# SH1_-_Buck_Converter.net
KiCad netlist of a schematic drawn in Altium Designer
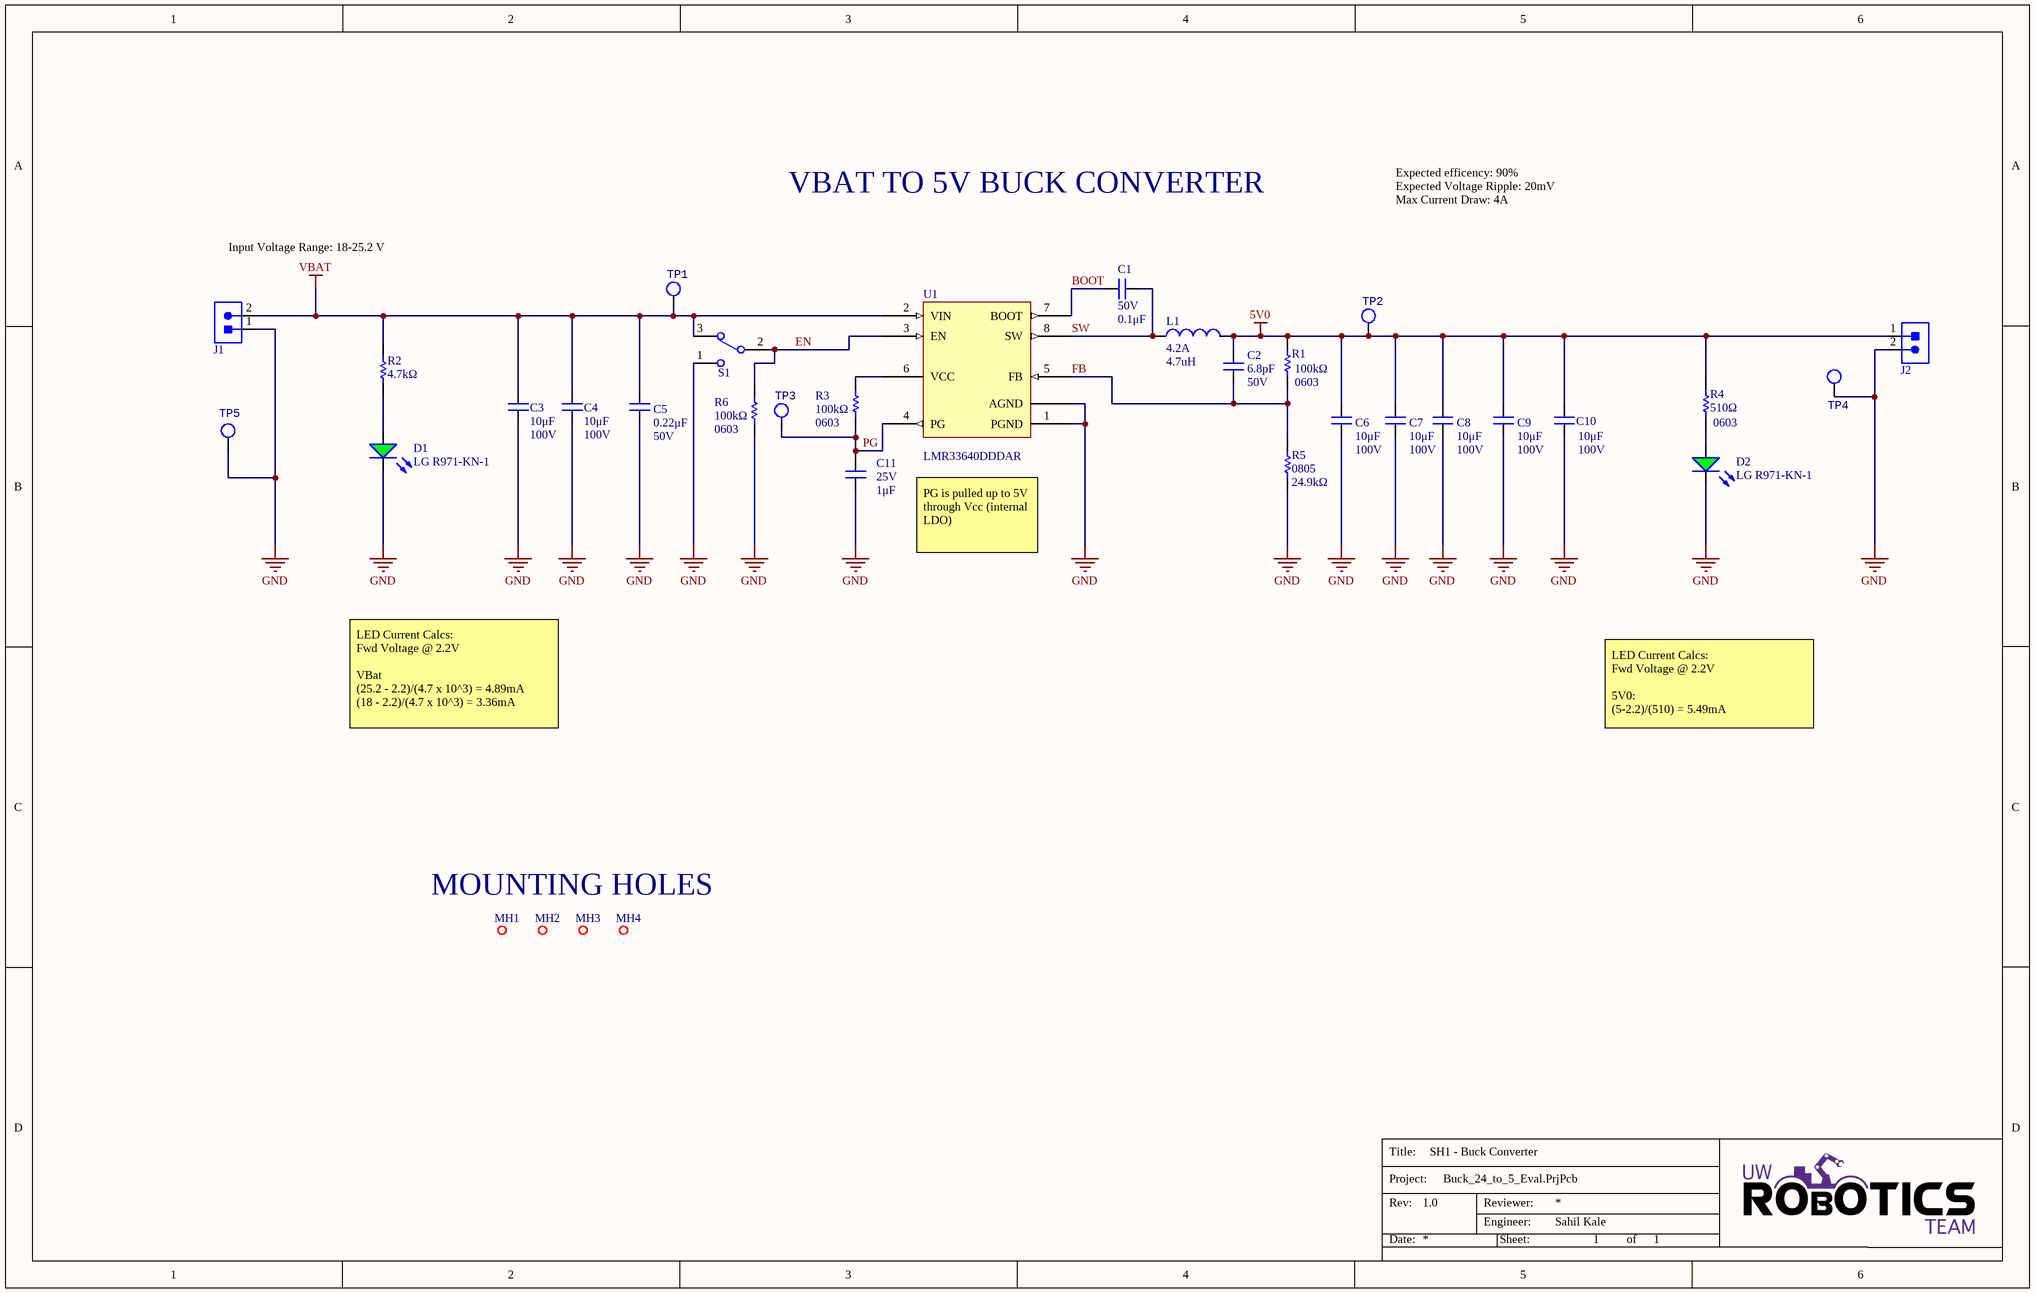
[diagram p0: SH1 - Buck Converter.SchDoc]

(export (version "E")
  (design (tool "Eeschema 10.0.6"))
  (components
    (comp (ref "C1")
      (value "0.1μF")
      (footprint "CAP0603")
      (description "CAP CER 0.1UF 50V X7R 0603")
      (fields (field (name "VOLTAGE RATING") "50V") (field (name "Comment") "CAP_0.1uF_50V_0603"))
      (libsource (lib "UWRT_Schematic_Library_2020") (part "CAP_0.1uF_50V_0603"))
    )
    (comp (ref "C2")
      (value "6.8pF")
      (footprint "CAP0603")
      (description "CAP CER 6.8PF 50V")
      (fields (field (name "VOLTAGE RATING") "50V") (field (name "Comment") "CAP_6.8pF_50V_0603"))
      (libsource (lib "UWRT_Schematic_Library_2020") (part "CAP_6.8pF_50V_0603"))
    )
    (comp (ref "C3")
      (value "10μF")
      (footprint "CAP1210")
      (description "CAP CER 10uF 100V X7S 10% 1210")
      (fields (field (name "VOLTAGE RATING") "100V") (field (name "Comment") "CAP_10uF_100V_1210"))
      (libsource (lib "UWRT_Schematic_Library_2020") (part "CAP_10uF_100V_1210"))
    )
    (comp (ref "C4")
      (value "10μF")
      (footprint "CAP1210")
      (description "CAP CER 10uF 100V X7S 10% 1210")
      (fields (field (name "VOLTAGE RATING") "100V") (field (name "Comment") "CAP_10uF_100V_1210"))
      (libsource (lib "UWRT_Schematic_Library_2020") (part "CAP_10uF_100V_1210"))
    )
    (comp (ref "C5")
      (value "0.22μF")
      (footprint "CAP2012")
      (description "CAP CER 0.22UF 50V X7R 0805")
      (fields
        (field (name "LCSC PART #") "C5378")
        (field (name "VOLTAGE RATING") "50V")
        (field (name "Comment") "CAP_0.22uF_50V_0805")
      )
      (libsource (lib "UWRT_Schematic_Library_2020") (part "CAP_0.22uF_50V_0805"))
    )
    (comp (ref "C6")
      (value "10μF")
      (footprint "CAP1210")
      (description "CAP CER 10uF 100V X7S 10% 1210")
      (fields (field (name "VOLTAGE RATING") "100V") (field (name "Comment") "CAP_10uF_100V_1210"))
      (libsource (lib "UWRT_Schematic_Library_2020") (part "CAP_10uF_100V_1210"))
    )
    (comp (ref "C7")
      (value "10μF")
      (footprint "CAP1210")
      (description "CAP CER 10uF 100V X7S 10% 1210")
      (fields (field (name "VOLTAGE RATING") "100V") (field (name "Comment") "CAP_10uF_100V_1210"))
      (libsource (lib "UWRT_Schematic_Library_2020") (part "CAP_10uF_100V_1210"))
    )
    (comp (ref "C8")
      (value "10μF")
      (footprint "CAP1210")
      (description "CAP CER 10uF 100V X7S 10% 1210")
      (fields (field (name "VOLTAGE RATING") "100V") (field (name "Comment") "CAP_10uF_100V_1210"))
      (libsource (lib "UWRT_Schematic_Library_2020") (part "CAP_10uF_100V_1210"))
    )
    (comp (ref "C9")
      (value "10μF")
      (footprint "CAP1210")
      (description "CAP CER 10uF 100V X7S 10% 1210")
      (fields (field (name "VOLTAGE RATING") "100V") (field (name "Comment") "CAP_10uF_100V_1210"))
      (libsource (lib "UWRT_Schematic_Library_2020") (part "CAP_10uF_100V_1210"))
    )
    (comp (ref "C10")
      (value "10μF")
      (footprint "CAP1210")
      (description "CAP CER 10uF 100V X7S 10% 1210")
      (fields (field (name "VOLTAGE RATING") "100V") (field (name "Comment") "CAP_10uF_100V_1210"))
      (libsource (lib "UWRT_Schematic_Library_2020") (part "CAP_10uF_100V_1210"))
    )
    (comp (ref "C11")
      (value "1μF")
      (footprint "CAP0603")
      (description "CAP CER 1UF 25V X5R 0603")
      (fields (field (name "VOLTAGE RATING") "25V") (field (name "Comment") "CAP_1uF_25V_0603"))
      (libsource (lib "UWRT_Schematic_Library_2020") (part "CAP_1uF_25V_0603"))
    )
    (comp (ref "D1")
      (value "LED_GREEN")
      (footprint "LED_0805_GREEN")
      (description "LED GREEN DIFFUSED 0805 SMD")
      (fields (field (name "MANUFACTURER PART NUMBER 1") "LG R971-KN-1"))
      (libsource (lib "UWRT_Schematic_Library_2020") (part "LED_GREEN"))
    )
    (comp (ref "D2")
      (value "LED_GREEN")
      (footprint "LED_0805_GREEN")
      (description "LED GREEN DIFFUSED 0805 SMD")
      (fields (field (name "MANUFACTURER PART NUMBER 1") "LG R971-KN-1"))
      (libsource (lib "UWRT_Schematic_Library_2020") (part "LED_GREEN"))
    )
    (comp (ref "J1")
      (value "CON_2POS_SCREW_TERM")
      (footprint "1935161")
      (description "TERM BLK 2POS SIDE ENTRY 5MM")
      (libsource (lib "") (part "CON_2POS_SCREW_TERM_1"))
    )
    (comp (ref "J2")
      (value "CON_2POS_SCREW_TERM")
      (footprint "1935161")
      (description "TERM BLK 2POS SIDE ENTRY 5MM")
      (libsource (lib "UWRT_Schematic_Library_2020") (part "CON_2POS_SCREW_TERM"))
    )
    (comp (ref "L1")
      (value "IND_4.7uH_4.2A")
      (footprint "VLS6045EX-4R7M")
      (description "FIXED IND 4.7UH 4.2A 35MOHM SMD")
      (fields
        (field (name "MANUFACTURER") "TDK")
        (field (name "TOLERANCE") "20%")
        (field (name "RATED CURRENT-MAX") "4.2A")
        (field (name "INDUCTANCE-NOM (L)") "4.7uH")
      )
      (libsource (lib "UWRT_Schematic_Library_2020") (part "IND_4.7uH_4.2A"))
    )
    (comp (ref "MH1")
      (value "MOUNTING_HOLE_M3")
      (footprint "MOUNTING_HOLE_3mm")
      (libsource (lib "UWRT_Schematic_Library_2020") (part "MOUNTING_HOLE_M3"))
    )
    (comp (ref "MH2")
      (value "MOUNTING_HOLE_M3")
      (footprint "MOUNTING_HOLE_3mm")
      (libsource (lib "UWRT_Schematic_Library_2020") (part "MOUNTING_HOLE_M3"))
    )
    (comp (ref "MH3")
      (value "MOUNTING_HOLE_M3")
      (footprint "MOUNTING_HOLE_3mm")
      (libsource (lib "UWRT_Schematic_Library_2020") (part "MOUNTING_HOLE_M3"))
    )
    (comp (ref "MH4")
      (value "MOUNTING_HOLE_M3")
      (footprint "MOUNTING_HOLE_3mm")
      (libsource (lib "UWRT_Schematic_Library_2020") (part "MOUNTING_HOLE_M3"))
    )
    (comp (ref "R1")
      (value "100kΩ")
      (footprint "RESC0603")
      (description "RES 100K OHM 1% 1/10W 0603")
      (fields (field (name "PACKAGE/FOOTPRINT") "0603") (field (name "Comment") "RES_100kΩ_0603_1%"))
      (libsource (lib "UWRT_Schematic_Library_2020") (part "RES_100kΩ_0603_1%"))
    )
    (comp (ref "R2")
      (value "4.7kΩ")
      (footprint "RESC0603")
      (description "RES 4.7K OHM 5% 1/10W 0603")
      (fields (field (name "Comment") "RES_4.7kΩ_0603"))
      (libsource (lib "UWRT_Schematic_Library_2020") (part "RES_4.7kΩ_0603_5%"))
    )
    (comp (ref "R3")
      (value "100kΩ")
      (footprint "RESC0603")
      (description "RES 100K OHM 1% 1/10W 0603")
      (fields (field (name "PACKAGE/FOOTPRINT") "0603") (field (name "Comment") "RES_100kΩ_0603_1%"))
      (libsource (lib "UWRT_Schematic_Library_2020") (part "RES_100kΩ_0603_1%"))
    )
    (comp (ref "R4")
      (value "510Ω")
      (footprint "RESC0603")
      (description "RES 510 OHM 5% 1/10W 0603")
      (fields (field (name "PACKAGE") "0603") (field (name "Comment") "RES_510Ω_0603"))
      (libsource (lib "UWRT_Schematic_Library_2020") (part "RES_510Ω_0603_5%"))
    )
    (comp (ref "R5")
      (value "24.9kΩ")
      (footprint "RESC0805")
      (description "RES 24.9K OHM 1% 1/8W 0805")
      (fields (field (name "PACKAGE/FOOTPRINT") "0805") (field (name "Comment") "RES_24.9kΩ_0805_1%_1"))
      (libsource (lib "UWRT_Schematic_Library_2020") (part "RES_24.9kΩ_0805_1%_1"))
    )
    (comp (ref "R6")
      (value "100kΩ")
      (footprint "RESC0603")
      (description "RES 100K OHM 1% 1/10W 0603")
      (fields (field (name "PACKAGE/FOOTPRINT") "0603") (field (name "Comment") "RES_100kΩ_0603_1%"))
      (libsource (lib "UWRT_Schematic_Library_2020") (part "RES_100kΩ_0603_1%"))
    )
    (comp (ref "S1")
      (value "SW_TOGGLE_SPDT")
      (footprint "100SP1T1B4M2QE")
      (description "SWITCH TOGGLE SPDT 5A 120V")
      (libsource (lib "UWRT_Schematic_Library_2020") (part "SW_TOGGLE_SPDT"))
    )
    (comp (ref "TP1")
      (value "TESTPOINT_LOOP")
      (footprint "TESTPOINT_LOOP")
      (description "TESTPOINT THRUHOLE")
      (libsource (lib "UWRT_Schematic_Library_2020") (part "TESTPOINT_LOOP"))
    )
    (comp (ref "TP2")
      (value "TESTPOINT_LOOP")
      (footprint "TESTPOINT_LOOP")
      (description "TESTPOINT THRUHOLE")
      (libsource (lib "UWRT_Schematic_Library_2020") (part "TESTPOINT_LOOP"))
    )
    (comp (ref "TP3")
      (value "TESTPOINT_LOOP")
      (footprint "TESTPOINT_LOOP")
      (description "TESTPOINT THRUHOLE")
      (libsource (lib "UWRT_Schematic_Library_2020") (part "TESTPOINT_LOOP"))
    )
    (comp (ref "TP4")
      (value "TESTPOINT_LOOP")
      (footprint "TESTPOINT_LOOP")
      (description "TESTPOINT THRUHOLE")
      (libsource (lib "UWRT_Schematic_Library_2020") (part "TESTPOINT_LOOP"))
    )
    (comp (ref "TP5")
      (value "TESTPOINT_LOOP")
      (footprint "TESTPOINT_LOOP")
      (description "TESTPOINT THRUHOLE")
      (libsource (lib "UWRT_Schematic_Library_2020") (part "TESTPOINT_LOOP"))
    )
    (comp (ref "U1")
      (value "BUCK_LMR33640DDDAR")
      (footprint "8-SO PowerPad")
      (description "IC REG BUCK ADJUSTABLE 4A 8SOPWR")
      (fields
        (field (name "MANUFACTURER") "Texas Instruments")
        (field (name "MANUFACTURER PART NUMBER 1") "LMR33640DDDAR")
      )
      (libsource (lib "UWRT_Schematic_Library_2020") (part "BUCK_LMR33640DDDAR"))
    )
  )
  (nets
    (net (code "1") (name "/BOOT") (class "Default")
      (node (ref "C1") (pin "1") (pinfunction "1_1") (pintype "passive"))
      (node (ref "U1") (pin "7") (pinfunction "BOOT_7") (pintype "output"))
    )
    (net (code "2") (name "/EN") (class "Default")
      (node (ref "R6") (pin "2") (pinfunction "2_2") (pintype "passive"))
      (node (ref "S1") (pin "2") (pinfunction "2_2") (pintype "passive"))
      (node (ref "U1") (pin "3") (pinfunction "EN_3") (pintype "input"))
    )
    (net (code "3") (name "/FB") (class "Default")
      (node (ref "C2") (pin "1") (pinfunction "1_1") (pintype "passive"))
      (node (ref "R1") (pin "1") (pinfunction "1_1") (pintype "passive"))
      (node (ref "R5") (pin "2") (pinfunction "2_2") (pintype "passive"))
      (node (ref "U1") (pin "5") (pinfunction "FB_5") (pintype "input"))
    )
    (net (code "4") (name "/PG") (class "Default")
      (node (ref "C11") (pin "2") (pinfunction "2_2") (pintype "passive"))
      (node (ref "R3") (pin "1") (pinfunction "1_1") (pintype "passive"))
      (node (ref "TP3") (pin "1") (pintype "passive"))
      (node (ref "U1") (pin "4") (pinfunction "PG_4") (pintype "output"))
    )
    (net (code "5") (name "/SW") (class "Default")
      (node (ref "C1") (pin "2") (pinfunction "2_2") (pintype "passive"))
      (node (ref "L1") (pin "1") (pinfunction "1_1") (pintype "passive"))
      (node (ref "U1") (pin "8") (pinfunction "SW_8") (pintype "output"))
    )
    (net (code "6") (name "5V0") (class "Default")
      (node (ref "C10") (pin "2") (pinfunction "2_2") (pintype "passive"))
      (node (ref "C2") (pin "2") (pinfunction "2_2") (pintype "passive"))
      (node (ref "C6") (pin "2") (pinfunction "2_2") (pintype "passive"))
      (node (ref "C7") (pin "2") (pinfunction "2_2") (pintype "passive"))
      (node (ref "C8") (pin "2") (pinfunction "2_2") (pintype "passive"))
      (node (ref "C9") (pin "2") (pinfunction "2_2") (pintype "passive"))
      (node (ref "J2") (pin "1") (pinfunction "1_1") (pintype "passive"))
      (node (ref "L1") (pin "2") (pinfunction "2_2") (pintype "passive"))
      (node (ref "R1") (pin "2") (pinfunction "2_2") (pintype "passive"))
      (node (ref "R4") (pin "1") (pinfunction "1_1") (pintype "passive"))
      (node (ref "TP2") (pin "1") (pintype "passive"))
    )
    (net (code "7") (name "GND") (class "Default")
      (node (ref "C10") (pin "1") (pinfunction "1_1") (pintype "passive"))
      (node (ref "C11") (pin "1") (pinfunction "1_1") (pintype "passive"))
      (node (ref "C3") (pin "1") (pinfunction "1_1") (pintype "passive"))
      (node (ref "C4") (pin "1") (pinfunction "1_1") (pintype "passive"))
      (node (ref "C5") (pin "1") (pinfunction "1_1") (pintype "passive"))
      (node (ref "C6") (pin "1") (pinfunction "1_1") (pintype "passive"))
      (node (ref "C7") (pin "1") (pinfunction "1_1") (pintype "passive"))
      (node (ref "C8") (pin "1") (pinfunction "1_1") (pintype "passive"))
      (node (ref "C9") (pin "1") (pinfunction "1_1") (pintype "passive"))
      (node (ref "D1") (pin "2") (pinfunction "K_2") (pintype "passive"))
      (node (ref "D2") (pin "2") (pinfunction "K_2") (pintype "passive"))
      (node (ref "J1") (pin "1") (pinfunction "1_1") (pintype "passive"))
      (node (ref "J2") (pin "2") (pinfunction "2_2") (pintype "passive"))
      (node (ref "R5") (pin "1") (pinfunction "1_1") (pintype "passive"))
      (node (ref "R6") (pin "1") (pinfunction "1_1") (pintype "passive"))
      (node (ref "S1") (pin "1") (pinfunction "1_1") (pintype "passive"))
      (node (ref "TP4") (pin "1") (pintype "passive"))
      (node (ref "TP5") (pin "1") (pintype "passive"))
      (node (ref "U1") (pin "1") (pinfunction "PGND_1") (pintype "passive"))
      (node (ref "U1") (pin "9") (pinfunction "AGND_9") (pintype "passive"))
    )
    (net (code "8") (name "Net-(D1-A)") (class "Default")
      (node (ref "D1") (pin "1") (pinfunction "A_1") (pintype "passive"))
      (node (ref "R2") (pin "1") (pinfunction "1_1") (pintype "passive"))
    )
    (net (code "9") (name "Net-(D2-A)") (class "Default")
      (node (ref "D2") (pin "1") (pinfunction "A_1") (pintype "passive"))
      (node (ref "R4") (pin "2") (pinfunction "2_2") (pintype "passive"))
    )
    (net (code "10") (name "Net-(U1-VCC)") (class "Default")
      (node (ref "R3") (pin "2") (pinfunction "2_2") (pintype "passive"))
      (node (ref "U1") (pin "6") (pinfunction "VCC_6") (pintype "passive"))
    )
    (net (code "11") (name "VBAT") (class "Default")
      (node (ref "C3") (pin "2") (pinfunction "2_2") (pintype "passive"))
      (node (ref "C4") (pin "2") (pinfunction "2_2") (pintype "passive"))
      (node (ref "C5") (pin "2") (pinfunction "2_2") (pintype "passive"))
      (node (ref "J1") (pin "2") (pinfunction "2_2") (pintype "passive"))
      (node (ref "R2") (pin "2") (pinfunction "2_2") (pintype "passive"))
      (node (ref "S1") (pin "3") (pinfunction "3_3") (pintype "passive"))
      (node (ref "TP1") (pin "1") (pintype "passive"))
      (node (ref "U1") (pin "2") (pinfunction "VIN_2") (pintype "input"))
    )
  )
)
